# rtc.net
KiCad netlist of a schematic drawn in Altium Designer
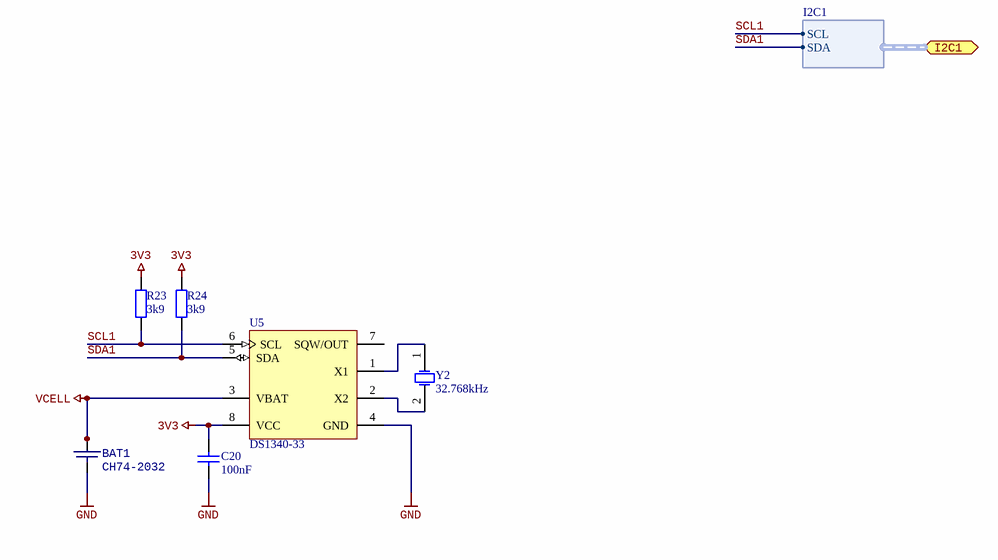
[diagram p0: rtc.SchDoc]

(export (version "E")
  (design (tool "Eeschema 10.0.6"))
  (components
    (comp (ref "BAT1")
      (value "CH74-2032")
      (footprint "BAT_2032_HOLDER")
      (libsource (lib "my_various_devices") (part "CH74-2032"))
    )
    (comp (ref "C20")
      (value "100nF")
      (footprint "CAPC1608N")
      (description "Capacitor")
      (libsource (lib "Discrete") (part "Capacitor"))
    )
    (comp (ref "R23")
      (value "3k9")
      (footprint "Chip_Resistor_N:RESC1608N")
      (description "Resistor")
      (fields (field (name "TOLERANCE") "5%") (field (name "POWER") "0W"))
      (libsource (lib "Discrete") (part "Resistor"))
    )
    (comp (ref "R24")
      (value "3k9")
      (footprint "Chip_Resistor_N:RESC1608N")
      (description "Resistor")
      (fields (field (name "TOLERANCE") "5%") (field (name "POWER") "0W"))
      (libsource (lib "Discrete") (part "Resistor"))
    )
    (comp (ref "U5")
      (value "DS1340-33")
      (footprint "Mechatronic:SO-8_L")
      (description "64 x 8, Serial, I2C Real-Time Clock, 5.0V, 8-Pin SO, -40 to 85 degC, Pb-Free")
      (libsource (lib "Altium Content Vault") (part "PR_RTC_DS1307-IL8"))
    )
    (comp (ref "Y2")
      (value "32.768kHz")
      (footprint "ABS25-crystal")
      (description "Crystal Oscillator")
      (libsource (lib "Discrete") (part "XTAL"))
    )
  )
  (nets
    (net (code "2") (name "/SCL1") (class "Default")
      (node (ref "R23") (pin "2") (pinfunction "2_2") (pintype "passive"))
      (node (ref "U5") (pin "6") (pinfunction "SCL_6") (pintype "input"))
    )
    (net (code "3") (name "/SDA1") (class "Default")
      (node (ref "R24") (pin "2") (pinfunction "2_2") (pintype "passive"))
      (node (ref "U5") (pin "5") (pinfunction "SDA_5") (pintype "bidirectional"))
    )
    (net (code "5") (name "3V3") (class "Default")
      (node (ref "C20") (pin "2") (pinfunction "2_2") (pintype "passive"))
      (node (ref "R23") (pin "1") (pinfunction "1_1") (pintype "passive"))
      (node (ref "R24") (pin "1") (pinfunction "1_1") (pintype "passive"))
      (node (ref "U5") (pin "8") (pinfunction "VCC_8") (pintype "power_in"))
    )
    (net (code "6") (name "GND") (class "Default")
      (node (ref "BAT1") (pin "3") (pinfunction "BAT-_3") (pintype "power_in"))
      (node (ref "C20") (pin "1") (pinfunction "1_1") (pintype "passive"))
      (node (ref "U5") (pin "4") (pinfunction "GND_4") (pintype "power_in"))
    )
    (net (code "7") (name "Net-(U5-X1)") (class "Default")
      (node (ref "U5") (pin "1") (pinfunction "X1_1") (pintype "passive"))
      (node (ref "Y2") (pin "1") (pinfunction "OSC1_1") (pintype "passive"))
    )
    (net (code "8") (name "Net-(U5-X2)") (class "Default")
      (node (ref "U5") (pin "2") (pinfunction "X2_2") (pintype "passive"))
      (node (ref "Y2") (pin "2") (pinfunction "OSC2_2") (pintype "passive"))
    )
    (net (code "9") (name "VCELL") (class "Default")
      (node (ref "BAT1") (pin "1") (pinfunction "BAT+_1") (pintype "power_in"))
      (node (ref "BAT1") (pin "2") (pinfunction "BAT+_2") (pintype "power_in"))
      (node (ref "U5") (pin "3") (pinfunction "VBAT_3") (pintype "power_in"))
    )
    (net (code "10") (name "unconnected-(U5-SQW{slash}OUT-Pad7)") (class "Default")
      (node (ref "U5") (pin "7") (pinfunction "SQW/OUT_7") (pintype "open_collector"))
    )
  )
)
